# SCH_Latencycam_2023-11-22.net
KiCad netlist of a schematic drawn in EasyEDA
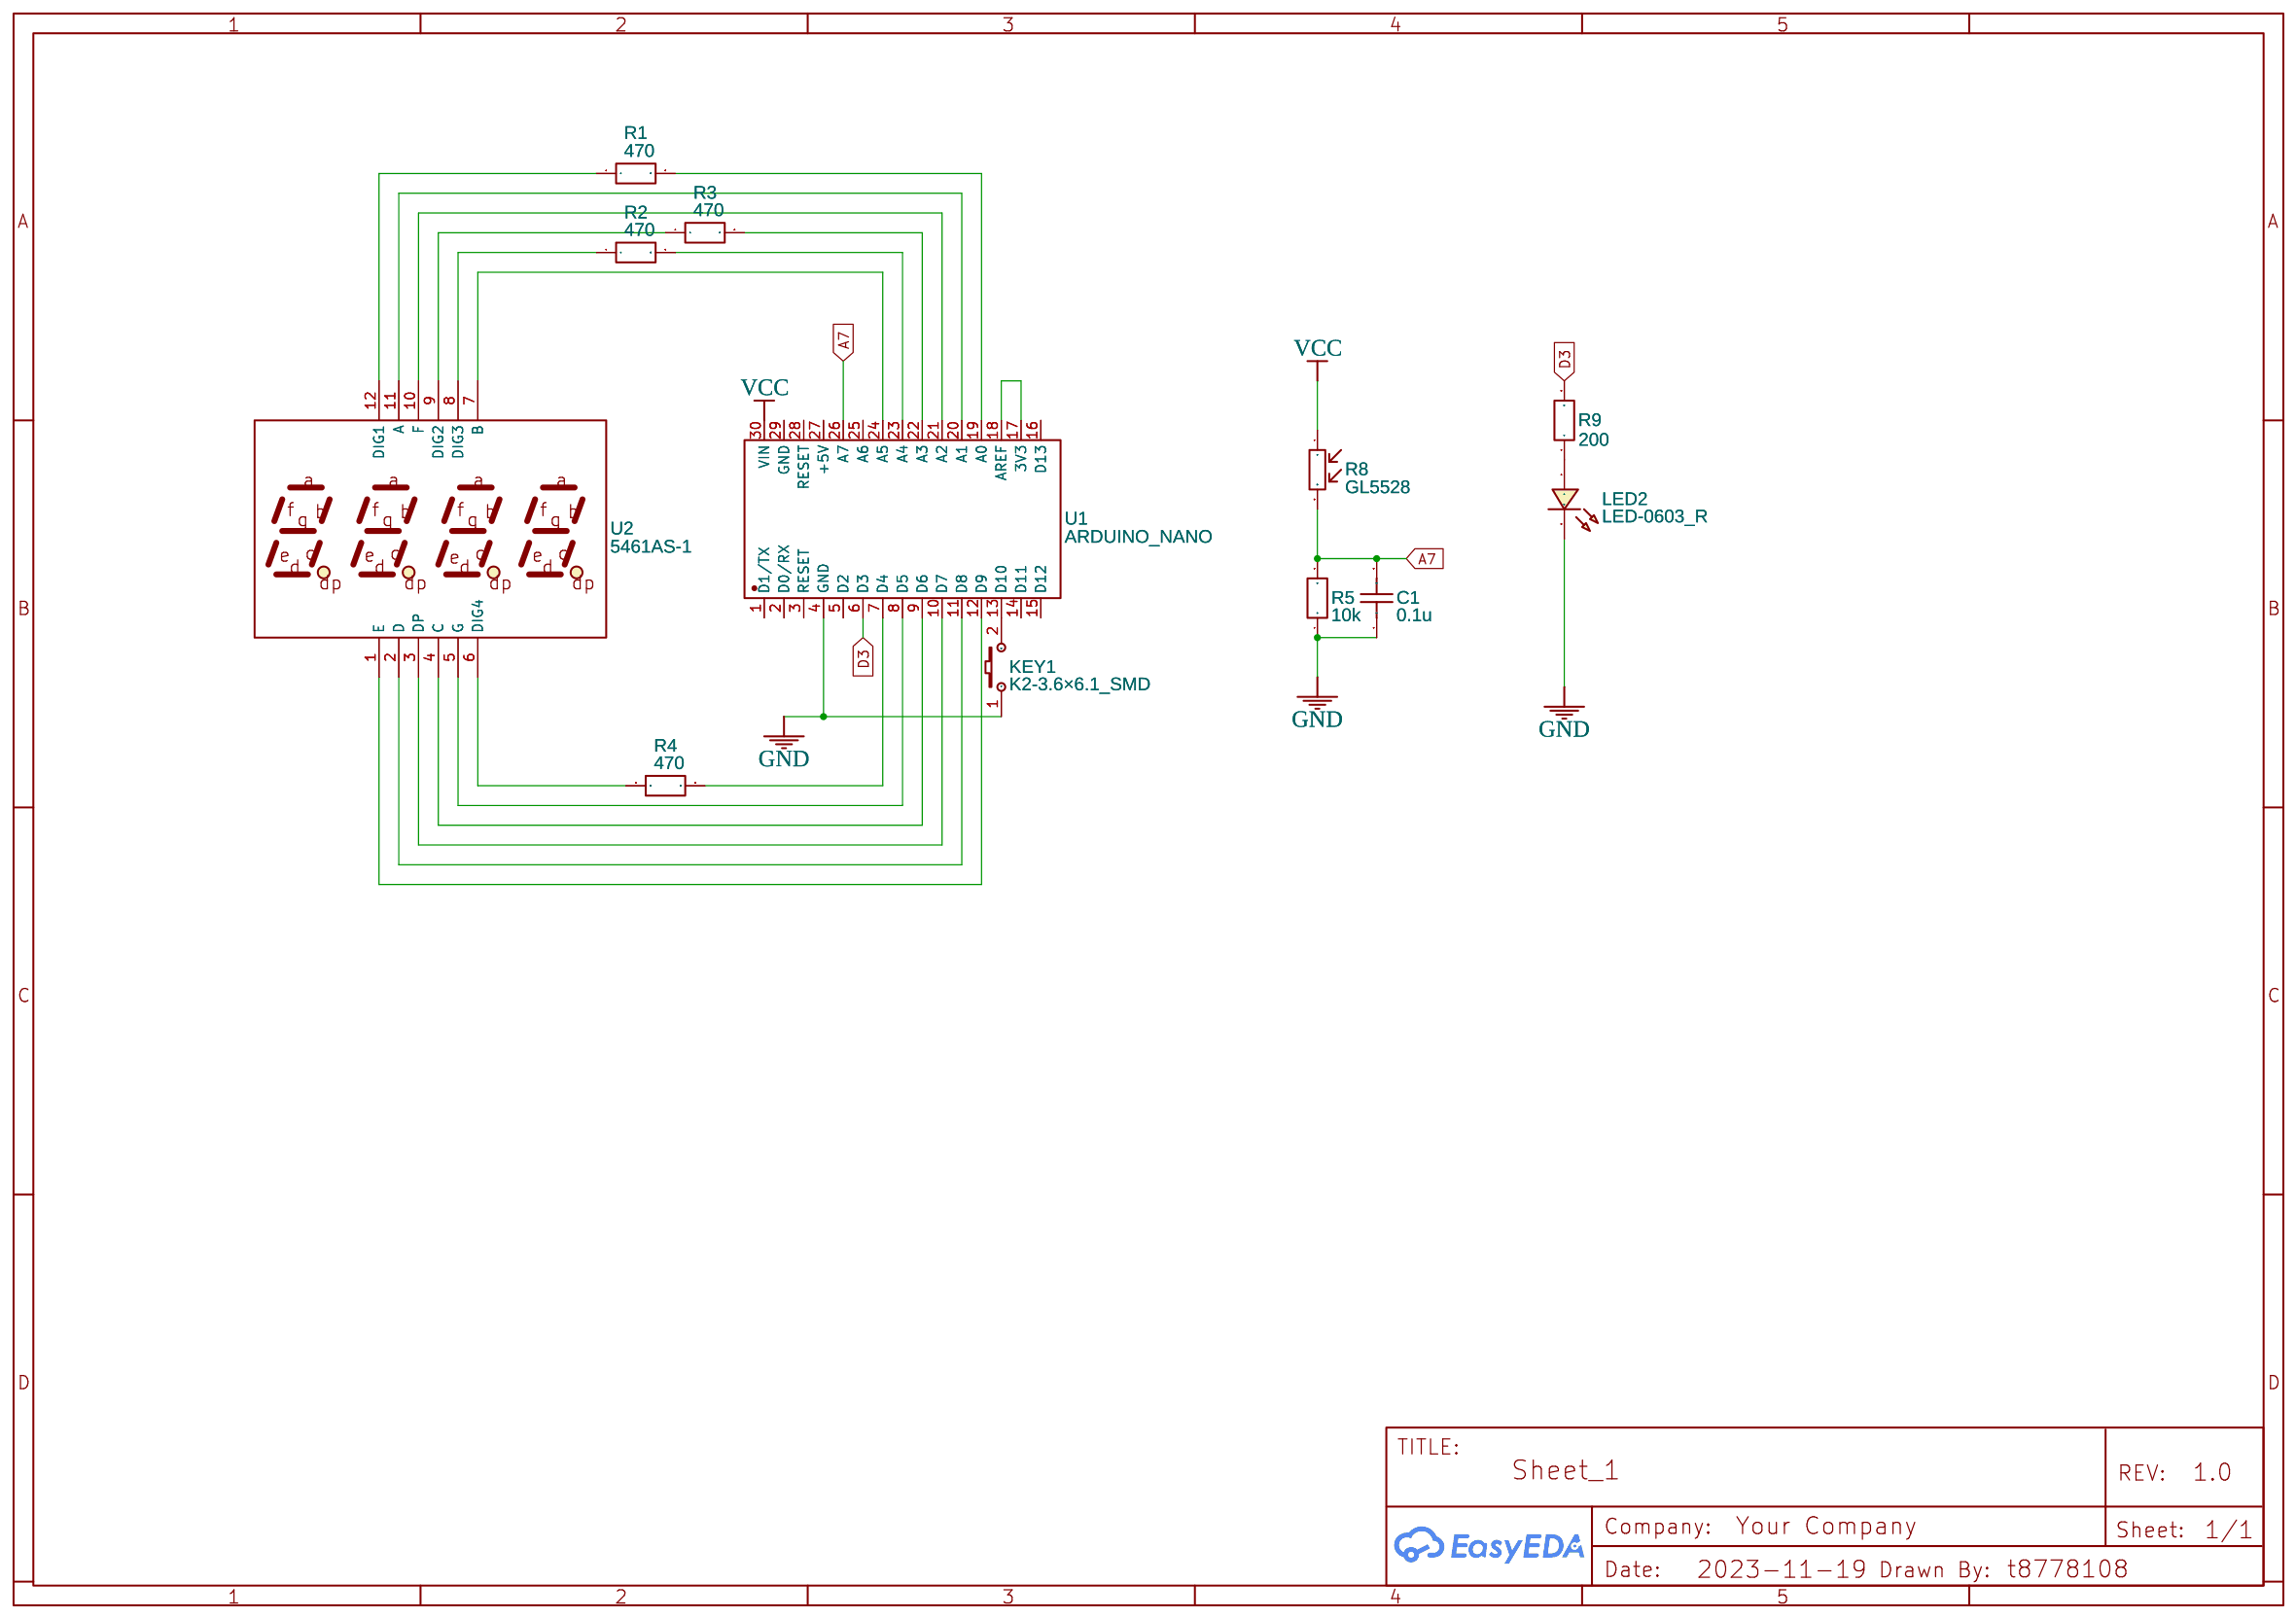
[diagram p0: schematic sheet]

(export (version "E")
  (design (tool "Eeschema 10.0.6"))
  (components
    (comp (ref "C1") (value "0.1u") (libsource (lib "") (part "C_0603_US")))
    (comp (ref "KEY1")
      (value "K2-3.6×6.1_SMD")
      (fields (field (name "Manufacturer Part") "K2-1107ST-A4SW-06"))
      (libsource (lib "") (part "K2-3.6×6.1_SMD"))
    )
    (comp (ref "LED2")
      (value "LED-0603_R")
      (fields
        (field (name "Manufacturer Part") "19-217/R6C-AL1M2VY/3T")
        (field (name "Manufacturer") "EVERLIGHT(台湾亿光)")
      )
      (libsource (lib "") (part "LED-0603_R"))
    )
    (comp (ref "R1") (value "470") (libsource (lib "") (part "R_0603_EU")))
    (comp (ref "R2") (value "470") (libsource (lib "") (part "R_0603_EU")))
    (comp (ref "R3") (value "470") (libsource (lib "") (part "R_0603_EU")))
    (comp (ref "R4") (value "470") (libsource (lib "") (part "R_0603_EU")))
    (comp (ref "R5") (value "10k") (libsource (lib "") (part "R_0603_EU_1")))
    (comp (ref "R8")
      (value "GL5528")
      (fields (field (name "Manufacturer") "森霸"))
      (libsource (lib "") (part "GL5528"))
    )
    (comp (ref "R9") (value "200") (libsource (lib "") (part "R_0603_EU_1")))
    (comp (ref "U1") (value "ARDUINO_NANO") (libsource (lib "") (part "ARDUINO_NANO")))
    (comp (ref "U2") (value "5461AS-1") (libsource (lib "") (part "5461AS-1")))
  )
  (nets
    (net (code "1") (name "A7") (class "Default")
      (node (ref "C1") (pin "2") (pinfunction "2_2") (pintype "unspecified"))
      (node (ref "R5") (pin "2") (pinfunction "2_2") (pintype "unspecified"))
      (node (ref "R8") (pin "2") (pinfunction "2_2") (pintype "input"))
      (node (ref "U1") (pin "26") (pinfunction "A7_26") (pintype "unspecified"))
    )
    (net (code "2") (name "D3") (class "Default")
      (node (ref "R9") (pin "2") (pinfunction "2_2") (pintype "unspecified"))
      (node (ref "U1") (pin "6") (pinfunction "D3_6") (pintype "unspecified"))
    )
    (net (code "3") (name "GND") (class "Default")
      (node (ref "C1") (pin "1") (pinfunction "1_1") (pintype "unspecified"))
      (node (ref "KEY1") (pin "1") (pinfunction "1_1") (pintype "unspecified"))
      (node (ref "LED2") (pin "2") (pinfunction "2_2") (pintype "unspecified"))
      (node (ref "R5") (pin "1") (pinfunction "1_1") (pintype "unspecified"))
      (node (ref "U1") (pin "4") (pinfunction "GND_4") (pintype "unspecified"))
    )
    (net (code "4") (name "Net-(LED2-Pad1)") (class "Default")
      (node (ref "LED2") (pin "1") (pinfunction "1_1") (pintype "unspecified"))
      (node (ref "R9") (pin "1") (pinfunction "1_1") (pintype "unspecified"))
    )
    (net (code "5") (name "Net-(U1-3V3)") (class "Default")
      (node (ref "U1") (pin "17") (pinfunction "3V3_17") (pintype "unspecified"))
      (node (ref "U1") (pin "18") (pinfunction "AREF_18") (pintype "unspecified"))
    )
    (net (code "6") (name "Net-(U1-A0)") (class "Default")
      (node (ref "R1") (pin "2") (pinfunction "2_2") (pintype "unspecified"))
      (node (ref "U1") (pin "19") (pinfunction "A0_19") (pintype "unspecified"))
    )
    (net (code "7") (name "Net-(U1-A1)") (class "Default")
      (node (ref "U1") (pin "20") (pinfunction "A1_20") (pintype "unspecified"))
      (node (ref "U2") (pin "11") (pinfunction "A_11") (pintype "input"))
    )
    (net (code "8") (name "Net-(U1-A2)") (class "Default")
      (node (ref "U1") (pin "21") (pinfunction "A2_21") (pintype "unspecified"))
      (node (ref "U2") (pin "10") (pinfunction "F_10") (pintype "input"))
    )
    (net (code "9") (name "Net-(U1-A3)") (class "Default")
      (node (ref "R3") (pin "2") (pinfunction "2_2") (pintype "unspecified"))
      (node (ref "U1") (pin "22") (pinfunction "A3_22") (pintype "unspecified"))
    )
    (net (code "10") (name "Net-(U1-A4)") (class "Default")
      (node (ref "R2") (pin "2") (pinfunction "2_2") (pintype "unspecified"))
      (node (ref "U1") (pin "23") (pinfunction "A4_23") (pintype "unspecified"))
    )
    (net (code "11") (name "Net-(U1-A5)") (class "Default")
      (node (ref "U1") (pin "24") (pinfunction "A5_24") (pintype "unspecified"))
      (node (ref "U2") (pin "7") (pinfunction "B_7") (pintype "input"))
    )
    (net (code "12") (name "Net-(U1-D4)") (class "Default")
      (node (ref "R4") (pin "2") (pinfunction "2_2") (pintype "unspecified"))
      (node (ref "U1") (pin "7") (pinfunction "D4_7") (pintype "unspecified"))
    )
    (net (code "13") (name "Net-(U1-D5)") (class "Default")
      (node (ref "U1") (pin "8") (pinfunction "D5_8") (pintype "unspecified"))
      (node (ref "U2") (pin "5") (pinfunction "G_5") (pintype "input"))
    )
    (net (code "14") (name "Net-(U1-D6)") (class "Default")
      (node (ref "U1") (pin "9") (pinfunction "D6_9") (pintype "unspecified"))
      (node (ref "U2") (pin "4") (pinfunction "C_4") (pintype "input"))
    )
    (net (code "15") (name "Net-(U1-D7)") (class "Default")
      (node (ref "U1") (pin "10") (pinfunction "D7_10") (pintype "unspecified"))
      (node (ref "U2") (pin "3") (pinfunction "DP_3") (pintype "input"))
    )
    (net (code "16") (name "Net-(U1-D8)") (class "Default")
      (node (ref "U1") (pin "11") (pinfunction "D8_11") (pintype "unspecified"))
      (node (ref "U2") (pin "2") (pinfunction "D_2") (pintype "input"))
    )
    (net (code "17") (name "Net-(U1-D9)") (class "Default")
      (node (ref "U1") (pin "12") (pinfunction "D9_12") (pintype "unspecified"))
      (node (ref "U2") (pin "1") (pinfunction "E_1") (pintype "input"))
    )
    (net (code "18") (name "Net-(U1-D10)") (class "Default")
      (node (ref "KEY1") (pin "2") (pinfunction "2_2") (pintype "unspecified"))
      (node (ref "U1") (pin "13") (pinfunction "D10_13") (pintype "unspecified"))
    )
    (net (code "19") (name "Net-(U2-DIG1)") (class "Default")
      (node (ref "R1") (pin "1") (pinfunction "1_1") (pintype "unspecified"))
      (node (ref "U2") (pin "12") (pinfunction "DIG1_12") (pintype "input"))
    )
    (net (code "20") (name "Net-(U2-DIG2)") (class "Default")
      (node (ref "R3") (pin "1") (pinfunction "1_1") (pintype "unspecified"))
      (node (ref "U2") (pin "9") (pinfunction "DIG2_9") (pintype "input"))
    )
    (net (code "21") (name "Net-(U2-DIG3)") (class "Default")
      (node (ref "R2") (pin "1") (pinfunction "1_1") (pintype "unspecified"))
      (node (ref "U2") (pin "8") (pinfunction "DIG3_8") (pintype "input"))
    )
    (net (code "22") (name "Net-(U2-DIG4)") (class "Default")
      (node (ref "R4") (pin "1") (pinfunction "1_1") (pintype "unspecified"))
      (node (ref "U2") (pin "6") (pinfunction "DIG4_6") (pintype "input"))
    )
    (net (code "23") (name "VCC") (class "Default")
      (node (ref "R8") (pin "1") (pinfunction "1_1") (pintype "input"))
      (node (ref "U1") (pin "30") (pinfunction "VIN_30") (pintype "unspecified"))
    )
    (net (code "24") (name "unconnected-(U1-+5V-Pad27)") (class "Default")
      (node (ref "U1") (pin "27") (pinfunction "+5V_27") (pintype "unspecified"))
    )
    (net (code "25") (name "unconnected-(U1-A6-Pad25)") (class "Default")
      (node (ref "U1") (pin "25") (pinfunction "A6_25") (pintype "unspecified"))
    )
    (net (code "26") (name "unconnected-(U1-D0{slash}RX-Pad2)") (class "Default")
      (node (ref "U1") (pin "2") (pinfunction "D0/RX_2") (pintype "unspecified"))
    )
    (net (code "27") (name "unconnected-(U1-D1{slash}TX-Pad1)") (class "Default")
      (node (ref "U1") (pin "1") (pinfunction "D1/TX_1") (pintype "unspecified"))
    )
    (net (code "28") (name "unconnected-(U1-D2-Pad5)") (class "Default")
      (node (ref "U1") (pin "5") (pinfunction "D2_5") (pintype "unspecified"))
    )
    (net (code "29") (name "unconnected-(U1-D11-Pad14)") (class "Default")
      (node (ref "U1") (pin "14") (pinfunction "D11_14") (pintype "unspecified"))
    )
    (net (code "30") (name "unconnected-(U1-D12-Pad15)") (class "Default")
      (node (ref "U1") (pin "15") (pinfunction "D12_15") (pintype "unspecified"))
    )
    (net (code "31") (name "unconnected-(U1-D13-Pad16)") (class "Default")
      (node (ref "U1") (pin "16") (pinfunction "D13_16") (pintype "unspecified"))
    )
    (net (code "32") (name "unconnected-(U1-GND-Pad29)") (class "Default")
      (node (ref "U1") (pin "29") (pinfunction "GND_29") (pintype "unspecified"))
    )
    (net (code "33") (name "unconnected-(U1-RESET-Pad3)") (class "Default")
      (node (ref "U1") (pin "3") (pinfunction "RESET_3") (pintype "unspecified"))
    )
    (net (code "34") (name "unconnected-(U1-RESET-Pad28)") (class "Default")
      (node (ref "U1") (pin "28") (pinfunction "RESET_28") (pintype "unspecified"))
    )
  )
)
